# 8bitPig-BaconHomev2-frontPCB.net
KiCad netlist of a schematic drawn in EAGLE
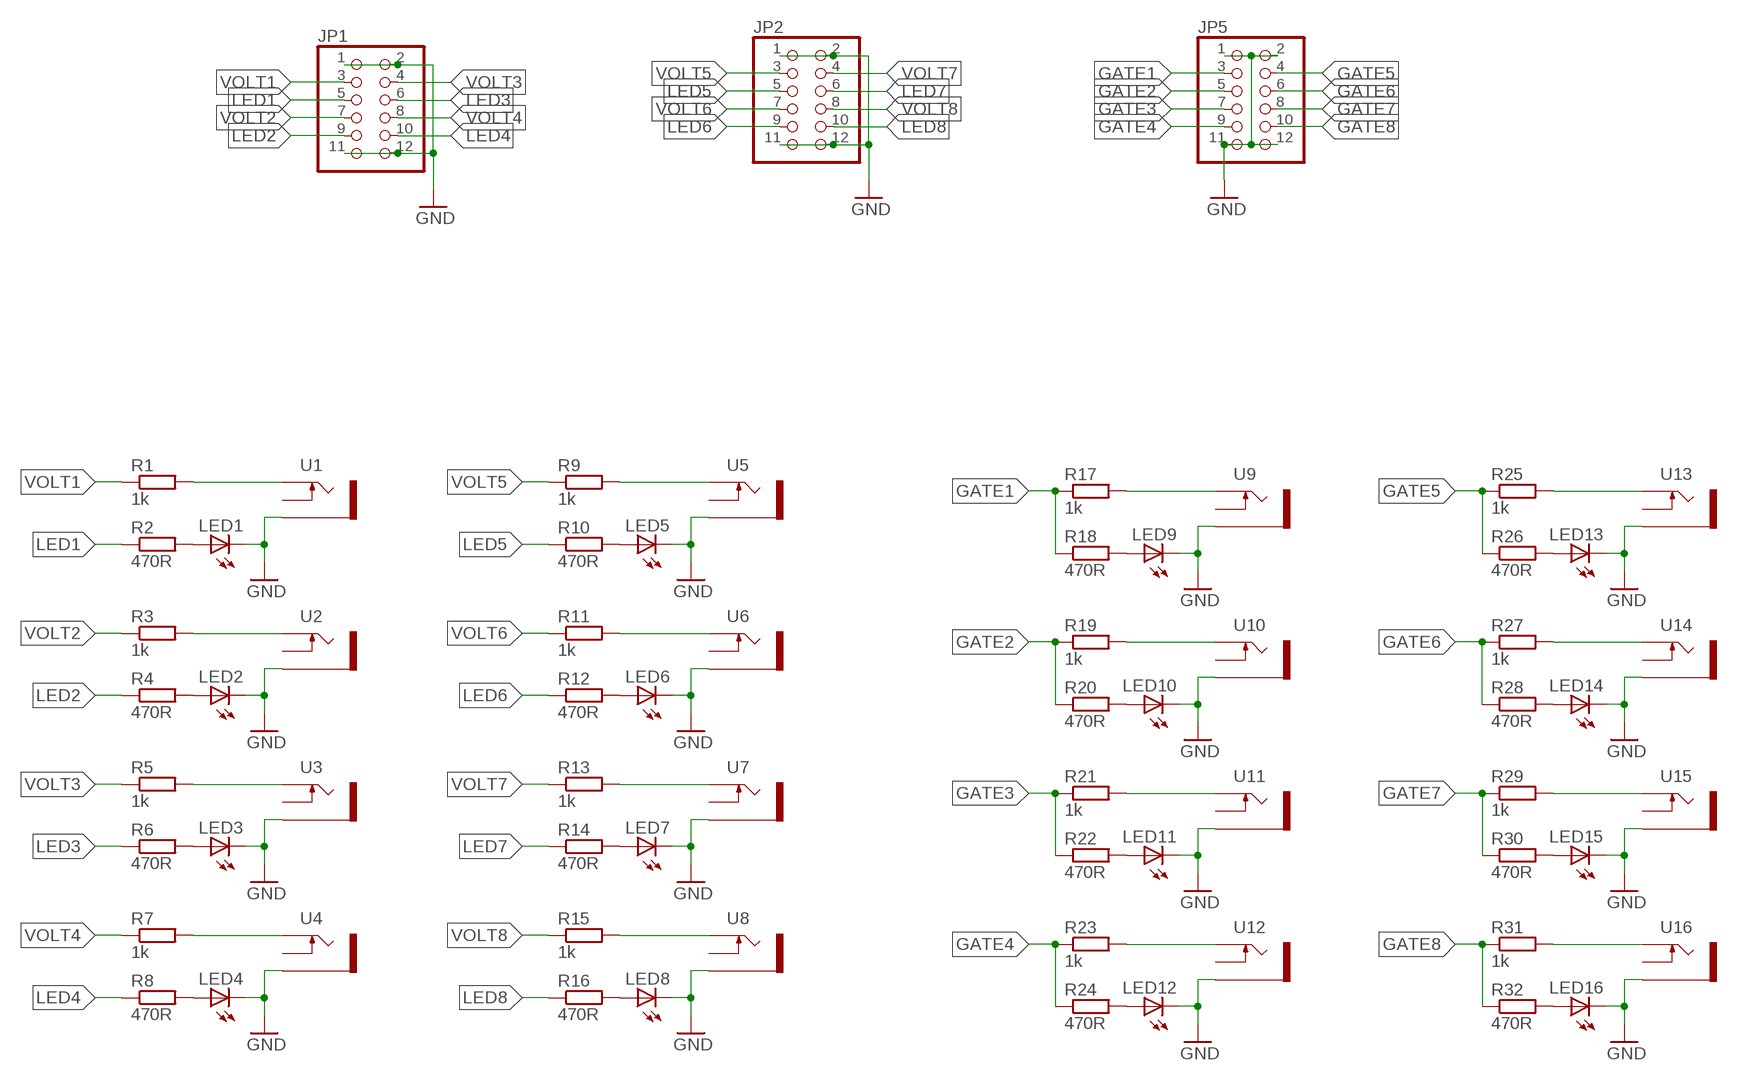
[diagram p0: schematic, sheet 1]

(export (version "E")
  (design (tool "Eeschema 10.0.6"))
  (components
    (comp (ref "JP1")
      (value "PINHD-2X6")
      (footprint "eagle-import:2X06")
      (libsource (lib "eagle-import") (part "PINHD-2X6"))
    )
    (comp (ref "JP2")
      (value "PINHD-2X6")
      (footprint "eagle-import:2X06")
      (libsource (lib "eagle-import") (part "PINHD-2X6"))
    )
    (comp (ref "JP5")
      (value "PINHD-2X6")
      (footprint "eagle-import:2X06")
      (libsource (lib "eagle-import") (part "PINHD-2X6"))
    )
    (comp (ref "LED1")
      (value "LED3MM")
      (footprint "eagle-import:LED3MM")
      (libsource (lib "eagle-import") (part "LED3MM"))
    )
    (comp (ref "LED2")
      (value "LED3MM")
      (footprint "eagle-import:LED3MM")
      (libsource (lib "eagle-import") (part "LED3MM"))
    )
    (comp (ref "LED3")
      (value "LED3MM")
      (footprint "eagle-import:LED3MM")
      (libsource (lib "eagle-import") (part "LED3MM"))
    )
    (comp (ref "LED4")
      (value "LED3MM")
      (footprint "eagle-import:LED3MM")
      (libsource (lib "eagle-import") (part "LED3MM"))
    )
    (comp (ref "LED5")
      (value "LED3MM")
      (footprint "eagle-import:LED3MM")
      (libsource (lib "eagle-import") (part "LED3MM"))
    )
    (comp (ref "LED6")
      (value "LED3MM")
      (footprint "eagle-import:LED3MM")
      (libsource (lib "eagle-import") (part "LED3MM"))
    )
    (comp (ref "LED7")
      (value "LED3MM")
      (footprint "eagle-import:LED3MM")
      (libsource (lib "eagle-import") (part "LED3MM"))
    )
    (comp (ref "LED8")
      (value "LED3MM")
      (footprint "eagle-import:LED3MM")
      (libsource (lib "eagle-import") (part "LED3MM"))
    )
    (comp (ref "LED9")
      (value "LED3MM")
      (footprint "eagle-import:LED3MM")
      (libsource (lib "eagle-import") (part "LED3MM"))
    )
    (comp (ref "LED10")
      (value "LED3MM")
      (footprint "eagle-import:LED3MM")
      (libsource (lib "eagle-import") (part "LED3MM"))
    )
    (comp (ref "LED11")
      (value "LED3MM")
      (footprint "eagle-import:LED3MM")
      (libsource (lib "eagle-import") (part "LED3MM"))
    )
    (comp (ref "LED12")
      (value "LED3MM")
      (footprint "eagle-import:LED3MM")
      (libsource (lib "eagle-import") (part "LED3MM"))
    )
    (comp (ref "LED13")
      (value "LED3MM")
      (footprint "eagle-import:LED3MM")
      (libsource (lib "eagle-import") (part "LED3MM"))
    )
    (comp (ref "LED14")
      (value "LED3MM")
      (footprint "eagle-import:LED3MM")
      (libsource (lib "eagle-import") (part "LED3MM"))
    )
    (comp (ref "LED15")
      (value "LED3MM")
      (footprint "eagle-import:LED3MM")
      (libsource (lib "eagle-import") (part "LED3MM"))
    )
    (comp (ref "LED16")
      (value "LED3MM")
      (footprint "eagle-import:LED3MM")
      (libsource (lib "eagle-import") (part "LED3MM"))
    )
    (comp (ref "R1")
      (value "1k")
      (footprint "eagle-import:R0603")
      (libsource (lib "eagle-import") (part "R-EU_R0603"))
    )
    (comp (ref "R2")
      (value "470R")
      (footprint "eagle-import:R0603")
      (libsource (lib "eagle-import") (part "R-EU_R0603"))
    )
    (comp (ref "R3")
      (value "1k")
      (footprint "eagle-import:R0603")
      (libsource (lib "eagle-import") (part "R-EU_R0603"))
    )
    (comp (ref "R4")
      (value "470R")
      (footprint "eagle-import:R0603")
      (libsource (lib "eagle-import") (part "R-EU_R0603"))
    )
    (comp (ref "R5")
      (value "1k")
      (footprint "eagle-import:R0603")
      (libsource (lib "eagle-import") (part "R-EU_R0603"))
    )
    (comp (ref "R6")
      (value "470R")
      (footprint "eagle-import:R0603")
      (libsource (lib "eagle-import") (part "R-EU_R0603"))
    )
    (comp (ref "R7")
      (value "1k")
      (footprint "eagle-import:R0603")
      (libsource (lib "eagle-import") (part "R-EU_R0603"))
    )
    (comp (ref "R8")
      (value "470R")
      (footprint "eagle-import:R0603")
      (libsource (lib "eagle-import") (part "R-EU_R0603"))
    )
    (comp (ref "R9")
      (value "1k")
      (footprint "eagle-import:R0603")
      (libsource (lib "eagle-import") (part "R-EU_R0603"))
    )
    (comp (ref "R10")
      (value "470R")
      (footprint "eagle-import:R0603")
      (libsource (lib "eagle-import") (part "R-EU_R0603"))
    )
    (comp (ref "R11")
      (value "1k")
      (footprint "eagle-import:R0603")
      (libsource (lib "eagle-import") (part "R-EU_R0603"))
    )
    (comp (ref "R12")
      (value "470R")
      (footprint "eagle-import:R0603")
      (libsource (lib "eagle-import") (part "R-EU_R0603"))
    )
    (comp (ref "R13")
      (value "1k")
      (footprint "eagle-import:R0603")
      (libsource (lib "eagle-import") (part "R-EU_R0603"))
    )
    (comp (ref "R14")
      (value "470R")
      (footprint "eagle-import:R0603")
      (libsource (lib "eagle-import") (part "R-EU_R0603"))
    )
    (comp (ref "R15")
      (value "1k")
      (footprint "eagle-import:R0603")
      (libsource (lib "eagle-import") (part "R-EU_R0603"))
    )
    (comp (ref "R16")
      (value "470R")
      (footprint "eagle-import:R0603")
      (libsource (lib "eagle-import") (part "R-EU_R0603"))
    )
    (comp (ref "R17")
      (value "1k")
      (footprint "eagle-import:R0603")
      (libsource (lib "eagle-import") (part "R-EU_R0603"))
    )
    (comp (ref "R18")
      (value "470R")
      (footprint "eagle-import:R0603")
      (libsource (lib "eagle-import") (part "R-EU_R0603"))
    )
    (comp (ref "R19")
      (value "1k")
      (footprint "eagle-import:R0603")
      (libsource (lib "eagle-import") (part "R-EU_R0603"))
    )
    (comp (ref "R20")
      (value "470R")
      (footprint "eagle-import:R0603")
      (libsource (lib "eagle-import") (part "R-EU_R0603"))
    )
    (comp (ref "R21")
      (value "1k")
      (footprint "eagle-import:R0603")
      (libsource (lib "eagle-import") (part "R-EU_R0603"))
    )
    (comp (ref "R22")
      (value "470R")
      (footprint "eagle-import:R0603")
      (libsource (lib "eagle-import") (part "R-EU_R0603"))
    )
    (comp (ref "R23")
      (value "1k")
      (footprint "eagle-import:R0603")
      (libsource (lib "eagle-import") (part "R-EU_R0603"))
    )
    (comp (ref "R24")
      (value "470R")
      (footprint "eagle-import:R0603")
      (libsource (lib "eagle-import") (part "R-EU_R0603"))
    )
    (comp (ref "R25")
      (value "1k")
      (footprint "eagle-import:R0603")
      (libsource (lib "eagle-import") (part "R-EU_R0603"))
    )
    (comp (ref "R26")
      (value "470R")
      (footprint "eagle-import:R0603")
      (libsource (lib "eagle-import") (part "R-EU_R0603"))
    )
    (comp (ref "R27")
      (value "1k")
      (footprint "eagle-import:R0603")
      (libsource (lib "eagle-import") (part "R-EU_R0603"))
    )
    (comp (ref "R28")
      (value "470R")
      (footprint "eagle-import:R0603")
      (libsource (lib "eagle-import") (part "R-EU_R0603"))
    )
    (comp (ref "R29")
      (value "1k")
      (footprint "eagle-import:R0603")
      (libsource (lib "eagle-import") (part "R-EU_R0603"))
    )
    (comp (ref "R30")
      (value "470R")
      (footprint "eagle-import:R0603")
      (libsource (lib "eagle-import") (part "R-EU_R0603"))
    )
    (comp (ref "R31")
      (value "1k")
      (footprint "eagle-import:R0603")
      (libsource (lib "eagle-import") (part "R-EU_R0603"))
    )
    (comp (ref "R32")
      (value "470R")
      (footprint "eagle-import:R0603")
      (libsource (lib "eagle-import") (part "R-EU_R0603"))
    )
    (comp (ref "U1")
      (value "THONKICONNNEW")
      (footprint "eagle-import:WQP-PJ301M-12_JACK")
      (libsource (lib "eagle-import") (part "THONKICONNNEW"))
    )
    (comp (ref "U2")
      (value "THONKICONNNEW")
      (footprint "eagle-import:WQP-PJ301M-12_JACK")
      (libsource (lib "eagle-import") (part "THONKICONNNEW"))
    )
    (comp (ref "U3")
      (value "THONKICONNNEW")
      (footprint "eagle-import:WQP-PJ301M-12_JACK")
      (libsource (lib "eagle-import") (part "THONKICONNNEW"))
    )
    (comp (ref "U4")
      (value "THONKICONNNEW")
      (footprint "eagle-import:WQP-PJ301M-12_JACK")
      (libsource (lib "eagle-import") (part "THONKICONNNEW"))
    )
    (comp (ref "U5")
      (value "THONKICONNNEW")
      (footprint "eagle-import:WQP-PJ301M-12_JACK")
      (libsource (lib "eagle-import") (part "THONKICONNNEW"))
    )
    (comp (ref "U6")
      (value "THONKICONNNEW")
      (footprint "eagle-import:WQP-PJ301M-12_JACK")
      (libsource (lib "eagle-import") (part "THONKICONNNEW"))
    )
    (comp (ref "U7")
      (value "THONKICONNNEW")
      (footprint "eagle-import:WQP-PJ301M-12_JACK")
      (libsource (lib "eagle-import") (part "THONKICONNNEW"))
    )
    (comp (ref "U8")
      (value "THONKICONNNEW")
      (footprint "eagle-import:WQP-PJ301M-12_JACK")
      (libsource (lib "eagle-import") (part "THONKICONNNEW"))
    )
    (comp (ref "U9")
      (value "THONKICONNNEW")
      (footprint "eagle-import:WQP-PJ301M-12_JACK")
      (libsource (lib "eagle-import") (part "THONKICONNNEW"))
    )
    (comp (ref "U10")
      (value "THONKICONNNEW")
      (footprint "eagle-import:WQP-PJ301M-12_JACK")
      (libsource (lib "eagle-import") (part "THONKICONNNEW"))
    )
    (comp (ref "U11")
      (value "THONKICONNNEW")
      (footprint "eagle-import:WQP-PJ301M-12_JACK")
      (libsource (lib "eagle-import") (part "THONKICONNNEW"))
    )
    (comp (ref "U12")
      (value "THONKICONNNEW")
      (footprint "eagle-import:WQP-PJ301M-12_JACK")
      (libsource (lib "eagle-import") (part "THONKICONNNEW"))
    )
    (comp (ref "U13")
      (value "THONKICONNNEW")
      (footprint "eagle-import:WQP-PJ301M-12_JACK")
      (libsource (lib "eagle-import") (part "THONKICONNNEW"))
    )
    (comp (ref "U14")
      (value "THONKICONNNEW")
      (footprint "eagle-import:WQP-PJ301M-12_JACK")
      (libsource (lib "eagle-import") (part "THONKICONNNEW"))
    )
    (comp (ref "U15")
      (value "THONKICONNNEW")
      (footprint "eagle-import:WQP-PJ301M-12_JACK")
      (libsource (lib "eagle-import") (part "THONKICONNNEW"))
    )
    (comp (ref "U16")
      (value "THONKICONNNEW")
      (footprint "eagle-import:WQP-PJ301M-12_JACK")
      (libsource (lib "eagle-import") (part "THONKICONNNEW"))
    )
  )
  (nets
    (net (code "1") (name "GATE1") (class "Default")
      (node (ref "JP5") (pin "3") (pinfunction "3_3") (pintype "passive"))
      (node (ref "R17") (pin "1") (pinfunction "1_1") (pintype "passive"))
      (node (ref "R18") (pin "1") (pinfunction "1_1") (pintype "passive"))
    )
    (net (code "2") (name "GATE2") (class "Default")
      (node (ref "JP5") (pin "5") (pinfunction "5_5") (pintype "passive"))
      (node (ref "R19") (pin "1") (pinfunction "1_1") (pintype "passive"))
      (node (ref "R20") (pin "1") (pinfunction "1_1") (pintype "passive"))
    )
    (net (code "3") (name "GATE3") (class "Default")
      (node (ref "JP5") (pin "7") (pinfunction "7_7") (pintype "passive"))
      (node (ref "R21") (pin "1") (pinfunction "1_1") (pintype "passive"))
      (node (ref "R22") (pin "1") (pinfunction "1_1") (pintype "passive"))
    )
    (net (code "4") (name "GATE4") (class "Default")
      (node (ref "JP5") (pin "9") (pinfunction "9_9") (pintype "passive"))
      (node (ref "R23") (pin "1") (pinfunction "1_1") (pintype "passive"))
      (node (ref "R24") (pin "1") (pinfunction "1_1") (pintype "passive"))
    )
    (net (code "5") (name "GATE5") (class "Default")
      (node (ref "JP5") (pin "4") (pinfunction "4_4") (pintype "passive"))
      (node (ref "R25") (pin "1") (pinfunction "1_1") (pintype "passive"))
      (node (ref "R26") (pin "1") (pinfunction "1_1") (pintype "passive"))
    )
    (net (code "6") (name "GATE6") (class "Default")
      (node (ref "JP5") (pin "6") (pinfunction "6_6") (pintype "passive"))
      (node (ref "R27") (pin "1") (pinfunction "1_1") (pintype "passive"))
      (node (ref "R28") (pin "1") (pinfunction "1_1") (pintype "passive"))
    )
    (net (code "7") (name "GATE7") (class "Default")
      (node (ref "JP5") (pin "8") (pinfunction "8_8") (pintype "passive"))
      (node (ref "R29") (pin "1") (pinfunction "1_1") (pintype "passive"))
      (node (ref "R30") (pin "1") (pinfunction "1_1") (pintype "passive"))
    )
    (net (code "8") (name "GATE8") (class "Default")
      (node (ref "JP5") (pin "10") (pinfunction "10_10") (pintype "passive"))
      (node (ref "R31") (pin "1") (pinfunction "1_1") (pintype "passive"))
      (node (ref "R32") (pin "1") (pinfunction "1_1") (pintype "passive"))
    )
    (net (code "9") (name "GND") (class "Default")
      (node (ref "JP1") (pin "1") (pinfunction "1_1") (pintype "passive"))
      (node (ref "JP1") (pin "11") (pinfunction "11_11") (pintype "passive"))
      (node (ref "JP1") (pin "12") (pinfunction "12_12") (pintype "passive"))
      (node (ref "JP1") (pin "2") (pinfunction "2_2") (pintype "passive"))
      (node (ref "JP2") (pin "1") (pinfunction "1_1") (pintype "passive"))
      (node (ref "JP2") (pin "11") (pinfunction "11_11") (pintype "passive"))
      (node (ref "JP2") (pin "12") (pinfunction "12_12") (pintype "passive"))
      (node (ref "JP2") (pin "2") (pinfunction "2_2") (pintype "passive"))
      (node (ref "JP5") (pin "1") (pinfunction "1_1") (pintype "passive"))
      (node (ref "JP5") (pin "11") (pinfunction "11_11") (pintype "passive"))
      (node (ref "JP5") (pin "12") (pinfunction "12_12") (pintype "passive"))
      (node (ref "JP5") (pin "2") (pinfunction "2_2") (pintype "passive"))
      (node (ref "LED1") (pin "K") (pinfunction "C_K") (pintype "passive"))
      (node (ref "LED10") (pin "K") (pinfunction "C_K") (pintype "passive"))
      (node (ref "LED11") (pin "K") (pinfunction "C_K") (pintype "passive"))
      (node (ref "LED12") (pin "K") (pinfunction "C_K") (pintype "passive"))
      (node (ref "LED13") (pin "K") (pinfunction "C_K") (pintype "passive"))
      (node (ref "LED14") (pin "K") (pinfunction "C_K") (pintype "passive"))
      (node (ref "LED15") (pin "K") (pinfunction "C_K") (pintype "passive"))
      (node (ref "LED16") (pin "K") (pinfunction "C_K") (pintype "passive"))
      (node (ref "LED2") (pin "K") (pinfunction "C_K") (pintype "passive"))
      (node (ref "LED3") (pin "K") (pinfunction "C_K") (pintype "passive"))
      (node (ref "LED4") (pin "K") (pinfunction "C_K") (pintype "passive"))
      (node (ref "LED5") (pin "K") (pinfunction "C_K") (pintype "passive"))
      (node (ref "LED6") (pin "K") (pinfunction "C_K") (pintype "passive"))
      (node (ref "LED7") (pin "K") (pinfunction "C_K") (pintype "passive"))
      (node (ref "LED8") (pin "K") (pinfunction "C_K") (pintype "passive"))
      (node (ref "LED9") (pin "K") (pinfunction "C_K") (pintype "passive"))
      (node (ref "U1") (pin "P$3_SLEEVE") (pinfunction "SLEEVE_P$3_SLEEVE") (pintype "passive"))
      (node (ref "U10") (pin "P$3_SLEEVE") (pinfunction "SLEEVE_P$3_SLEEVE") (pintype "passive"))
      (node (ref "U11") (pin "P$3_SLEEVE") (pinfunction "SLEEVE_P$3_SLEEVE") (pintype "passive"))
      (node (ref "U12") (pin "P$3_SLEEVE") (pinfunction "SLEEVE_P$3_SLEEVE") (pintype "passive"))
      (node (ref "U13") (pin "P$3_SLEEVE") (pinfunction "SLEEVE_P$3_SLEEVE") (pintype "passive"))
      (node (ref "U14") (pin "P$3_SLEEVE") (pinfunction "SLEEVE_P$3_SLEEVE") (pintype "passive"))
      (node (ref "U15") (pin "P$3_SLEEVE") (pinfunction "SLEEVE_P$3_SLEEVE") (pintype "passive"))
      (node (ref "U16") (pin "P$3_SLEEVE") (pinfunction "SLEEVE_P$3_SLEEVE") (pintype "passive"))
      (node (ref "U2") (pin "P$3_SLEEVE") (pinfunction "SLEEVE_P$3_SLEEVE") (pintype "passive"))
      (node (ref "U3") (pin "P$3_SLEEVE") (pinfunction "SLEEVE_P$3_SLEEVE") (pintype "passive"))
      (node (ref "U4") (pin "P$3_SLEEVE") (pinfunction "SLEEVE_P$3_SLEEVE") (pintype "passive"))
      (node (ref "U5") (pin "P$3_SLEEVE") (pinfunction "SLEEVE_P$3_SLEEVE") (pintype "passive"))
      (node (ref "U6") (pin "P$3_SLEEVE") (pinfunction "SLEEVE_P$3_SLEEVE") (pintype "passive"))
      (node (ref "U7") (pin "P$3_SLEEVE") (pinfunction "SLEEVE_P$3_SLEEVE") (pintype "passive"))
      (node (ref "U8") (pin "P$3_SLEEVE") (pinfunction "SLEEVE_P$3_SLEEVE") (pintype "passive"))
      (node (ref "U9") (pin "P$3_SLEEVE") (pinfunction "SLEEVE_P$3_SLEEVE") (pintype "passive"))
    )
    (net (code "10") (name "LED1") (class "Default")
      (node (ref "JP1") (pin "5") (pinfunction "5_5") (pintype "passive"))
      (node (ref "R2") (pin "1") (pinfunction "1_1") (pintype "passive"))
    )
    (net (code "11") (name "LED2") (class "Default")
      (node (ref "JP1") (pin "9") (pinfunction "9_9") (pintype "passive"))
      (node (ref "R4") (pin "1") (pinfunction "1_1") (pintype "passive"))
    )
    (net (code "12") (name "LED3") (class "Default")
      (node (ref "JP1") (pin "6") (pinfunction "6_6") (pintype "passive"))
      (node (ref "R6") (pin "1") (pinfunction "1_1") (pintype "passive"))
    )
    (net (code "13") (name "LED4") (class "Default")
      (node (ref "JP1") (pin "10") (pinfunction "10_10") (pintype "passive"))
      (node (ref "R8") (pin "1") (pinfunction "1_1") (pintype "passive"))
    )
    (net (code "14") (name "LED5") (class "Default")
      (node (ref "JP2") (pin "5") (pinfunction "5_5") (pintype "passive"))
      (node (ref "R10") (pin "1") (pinfunction "1_1") (pintype "passive"))
    )
    (net (code "15") (name "LED6") (class "Default")
      (node (ref "JP2") (pin "9") (pinfunction "9_9") (pintype "passive"))
      (node (ref "R12") (pin "1") (pinfunction "1_1") (pintype "passive"))
    )
    (net (code "16") (name "LED7") (class "Default")
      (node (ref "JP2") (pin "6") (pinfunction "6_6") (pintype "passive"))
      (node (ref "R14") (pin "1") (pinfunction "1_1") (pintype "passive"))
    )
    (net (code "17") (name "LED8") (class "Default")
      (node (ref "JP2") (pin "10") (pinfunction "10_10") (pintype "passive"))
      (node (ref "R16") (pin "1") (pinfunction "1_1") (pintype "passive"))
    )
    (net (code "18") (name "Net-(LED1-PadA)") (class "Default")
      (node (ref "LED1") (pin "A") (pinfunction "A_A") (pintype "passive"))
      (node (ref "R2") (pin "2") (pinfunction "2_2") (pintype "passive"))
    )
    (net (code "19") (name "Net-(LED2-PadA)") (class "Default")
      (node (ref "LED2") (pin "A") (pinfunction "A_A") (pintype "passive"))
      (node (ref "R4") (pin "2") (pinfunction "2_2") (pintype "passive"))
    )
    (net (code "20") (name "Net-(LED3-PadA)") (class "Default")
      (node (ref "LED3") (pin "A") (pinfunction "A_A") (pintype "passive"))
      (node (ref "R6") (pin "2") (pinfunction "2_2") (pintype "passive"))
    )
    (net (code "21") (name "Net-(LED4-PadA)") (class "Default")
      (node (ref "LED4") (pin "A") (pinfunction "A_A") (pintype "passive"))
      (node (ref "R8") (pin "2") (pinfunction "2_2") (pintype "passive"))
    )
    (net (code "22") (name "Net-(LED5-PadA)") (class "Default")
      (node (ref "LED5") (pin "A") (pinfunction "A_A") (pintype "passive"))
      (node (ref "R10") (pin "2") (pinfunction "2_2") (pintype "passive"))
    )
    (net (code "23") (name "Net-(LED6-PadA)") (class "Default")
      (node (ref "LED6") (pin "A") (pinfunction "A_A") (pintype "passive"))
      (node (ref "R12") (pin "2") (pinfunction "2_2") (pintype "passive"))
    )
    (net (code "24") (name "Net-(LED7-PadA)") (class "Default")
      (node (ref "LED7") (pin "A") (pinfunction "A_A") (pintype "passive"))
      (node (ref "R14") (pin "2") (pinfunction "2_2") (pintype "passive"))
    )
    (net (code "25") (name "Net-(LED8-PadA)") (class "Default")
      (node (ref "LED8") (pin "A") (pinfunction "A_A") (pintype "passive"))
      (node (ref "R16") (pin "2") (pinfunction "2_2") (pintype "passive"))
    )
    (net (code "26") (name "Net-(LED9-PadA)") (class "Default")
      (node (ref "LED9") (pin "A") (pinfunction "A_A") (pintype "passive"))
      (node (ref "R18") (pin "2") (pinfunction "2_2") (pintype "passive"))
    )
    (net (code "27") (name "Net-(LED10-PadA)") (class "Default")
      (node (ref "LED10") (pin "A") (pinfunction "A_A") (pintype "passive"))
      (node (ref "R20") (pin "2") (pinfunction "2_2") (pintype "passive"))
    )
    (net (code "28") (name "Net-(LED11-PadA)") (class "Default")
      (node (ref "LED11") (pin "A") (pinfunction "A_A") (pintype "passive"))
      (node (ref "R22") (pin "2") (pinfunction "2_2") (pintype "passive"))
    )
    (net (code "29") (name "Net-(LED12-PadA)") (class "Default")
      (node (ref "LED12") (pin "A") (pinfunction "A_A") (pintype "passive"))
      (node (ref "R24") (pin "2") (pinfunction "2_2") (pintype "passive"))
    )
    (net (code "30") (name "Net-(LED13-PadA)") (class "Default")
      (node (ref "LED13") (pin "A") (pinfunction "A_A") (pintype "passive"))
      (node (ref "R26") (pin "2") (pinfunction "2_2") (pintype "passive"))
    )
    (net (code "31") (name "Net-(LED14-PadA)") (class "Default")
      (node (ref "LED14") (pin "A") (pinfunction "A_A") (pintype "passive"))
      (node (ref "R28") (pin "2") (pinfunction "2_2") (pintype "passive"))
    )
    (net (code "32") (name "Net-(LED15-PadA)") (class "Default")
      (node (ref "LED15") (pin "A") (pinfunction "A_A") (pintype "passive"))
      (node (ref "R30") (pin "2") (pinfunction "2_2") (pintype "passive"))
    )
    (net (code "33") (name "Net-(LED16-PadA)") (class "Default")
      (node (ref "LED16") (pin "A") (pinfunction "A_A") (pintype "passive"))
      (node (ref "R32") (pin "2") (pinfunction "2_2") (pintype "passive"))
    )
    (net (code "34") (name "Net-(U1-TIP)") (class "Default")
      (node (ref "R1") (pin "2") (pinfunction "2_2") (pintype "passive"))
      (node (ref "U1") (pin "P$1_TIP") (pinfunction "TIP_P$1_TIP") (pintype "passive"))
    )
    (net (code "35") (name "Net-(U2-TIP)") (class "Default")
      (node (ref "R3") (pin "2") (pinfunction "2_2") (pintype "passive"))
      (node (ref "U2") (pin "P$1_TIP") (pinfunction "TIP_P$1_TIP") (pintype "passive"))
    )
    (net (code "36") (name "Net-(U3-TIP)") (class "Default")
      (node (ref "R5") (pin "2") (pinfunction "2_2") (pintype "passive"))
      (node (ref "U3") (pin "P$1_TIP") (pinfunction "TIP_P$1_TIP") (pintype "passive"))
    )
    (net (code "37") (name "Net-(U4-TIP)") (class "Default")
      (node (ref "R7") (pin "2") (pinfunction "2_2") (pintype "passive"))
      (node (ref "U4") (pin "P$1_TIP") (pinfunction "TIP_P$1_TIP") (pintype "passive"))
    )
    (net (code "38") (name "Net-(U5-TIP)") (class "Default")
      (node (ref "R9") (pin "2") (pinfunction "2_2") (pintype "passive"))
      (node (ref "U5") (pin "P$1_TIP") (pinfunction "TIP_P$1_TIP") (pintype "passive"))
    )
    (net (code "39") (name "Net-(U6-TIP)") (class "Default")
      (node (ref "R11") (pin "2") (pinfunction "2_2") (pintype "passive"))
      (node (ref "U6") (pin "P$1_TIP") (pinfunction "TIP_P$1_TIP") (pintype "passive"))
    )
    (net (code "40") (name "Net-(U7-TIP)") (class "Default")
      (node (ref "R13") (pin "2") (pinfunction "2_2") (pintype "passive"))
      (node (ref "U7") (pin "P$1_TIP") (pinfunction "TIP_P$1_TIP") (pintype "passive"))
    )
    (net (code "41") (name "Net-(U8-TIP)") (class "Default")
      (node (ref "R15") (pin "2") (pinfunction "2_2") (pintype "passive"))
      (node (ref "U8") (pin "P$1_TIP") (pinfunction "TIP_P$1_TIP") (pintype "passive"))
    )
    (net (code "42") (name "Net-(U9-TIP)") (class "Default")
      (node (ref "R17") (pin "2") (pinfunction "2_2") (pintype "passive"))
      (node (ref "U9") (pin "P$1_TIP") (pinfunction "TIP_P$1_TIP") (pintype "passive"))
    )
    (net (code "43") (name "Net-(U10-TIP)") (class "Default")
      (node (ref "R19") (pin "2") (pinfunction "2_2") (pintype "passive"))
      (node (ref "U10") (pin "P$1_TIP") (pinfunction "TIP_P$1_TIP") (pintype "passive"))
    )
    (net (code "44") (name "Net-(U11-TIP)") (class "Default")
      (node (ref "R21") (pin "2") (pinfunction "2_2") (pintype "passive"))
      (node (ref "U11") (pin "P$1_TIP") (pinfunction "TIP_P$1_TIP") (pintype "passive"))
    )
    (net (code "45") (name "Net-(U12-TIP)") (class "Default")
      (node (ref "R23") (pin "2") (pinfunction "2_2") (pintype "passive"))
      (node (ref "U12") (pin "P$1_TIP") (pinfunction "TIP_P$1_TIP") (pintype "passive"))
    )
    (net (code "46") (name "Net-(U13-TIP)") (class "Default")
      (node (ref "R25") (pin "2") (pinfunction "2_2") (pintype "passive"))
      (node (ref "U13") (pin "P$1_TIP") (pinfunction "TIP_P$1_TIP") (pintype "passive"))
    )
    (net (code "47") (name "Net-(U14-TIP)") (class "Default")
      (node (ref "R27") (pin "2") (pinfunction "2_2") (pintype "passive"))
      (node (ref "U14") (pin "P$1_TIP") (pinfunction "TIP_P$1_TIP") (pintype "passive"))
    )
    (net (code "48") (name "Net-(U15-TIP)") (class "Default")
      (node (ref "R29") (pin "2") (pinfunction "2_2") (pintype "passive"))
      (node (ref "U15") (pin "P$1_TIP") (pinfunction "TIP_P$1_TIP") (pintype "passive"))
    )
    (net (code "49") (name "Net-(U16-TIP)") (class "Default")
      (node (ref "R31") (pin "2") (pinfunction "2_2") (pintype "passive"))
      (node (ref "U16") (pin "P$1_TIP") (pinfunction "TIP_P$1_TIP") (pintype "passive"))
    )
    (net (code "50") (name "VOLT1") (class "Default")
      (node (ref "JP1") (pin "3") (pinfunction "3_3") (pintype "passive"))
      (node (ref "R1") (pin "1") (pinfunction "1_1") (pintype "passive"))
    )
    (net (code "51") (name "VOLT2") (class "Default")
      (node (ref "JP1") (pin "7") (pinfunction "7_7") (pintype "passive"))
      (node (ref "R3") (pin "1") (pinfunction "1_1") (pintype "passive"))
    )
    (net (code "52") (name "VOLT3") (class "Default")
      (node (ref "JP1") (pin "4") (pinfunction "4_4") (pintype "passive"))
      (node (ref "R5") (pin "1") (pinfunction "1_1") (pintype "passive"))
    )
    (net (code "53") (name "VOLT4") (class "Default")
      (node (ref "JP1") (pin "8") (pinfunction "8_8") (pintype "passive"))
      (node (ref "R7") (pin "1") (pinfunction "1_1") (pintype "passive"))
    )
    (net (code "54") (name "VOLT5") (class "Default")
      (node (ref "JP2") (pin "3") (pinfunction "3_3") (pintype "passive"))
      (node (ref "R9") (pin "1") (pinfunction "1_1") (pintype "passive"))
    )
    (net (code "55") (name "VOLT6") (class "Default")
      (node (ref "JP2") (pin "7") (pinfunction "7_7") (pintype "passive"))
      (node (ref "R11") (pin "1") (pinfunction "1_1") (pintype "passive"))
    )
    (net (code "56") (name "VOLT7") (class "Default")
      (node (ref "JP2") (pin "4") (pinfunction "4_4") (pintype "passive"))
      (node (ref "R13") (pin "1") (pinfunction "1_1") (pintype "passive"))
    )
    (net (code "57") (name "VOLT8") (class "Default")
      (node (ref "JP2") (pin "8") (pinfunction "8_8") (pintype "passive"))
      (node (ref "R15") (pin "1") (pinfunction "1_1") (pintype "passive"))
    )
    (net (code "58") (name "unconnected-(U1-SWITCH-PadP$2_SWITCH)") (class "Default")
      (node (ref "U1") (pin "P$2_SWITCH") (pinfunction "SWITCH_P$2_SWITCH") (pintype "passive"))
    )
    (net (code "59") (name "unconnected-(U2-SWITCH-PadP$2_SWITCH)") (class "Default")
      (node (ref "U2") (pin "P$2_SWITCH") (pinfunction "SWITCH_P$2_SWITCH") (pintype "passive"))
    )
    (net (code "60") (name "unconnected-(U3-SWITCH-PadP$2_SWITCH)") (class "Default")
      (node (ref "U3") (pin "P$2_SWITCH") (pinfunction "SWITCH_P$2_SWITCH") (pintype "passive"))
    )
    (net (code "61") (name "unconnected-(U4-SWITCH-PadP$2_SWITCH)") (class "Default")
      (node (ref "U4") (pin "P$2_SWITCH") (pinfunction "SWITCH_P$2_SWITCH") (pintype "passive"))
    )
    (net (code "62") (name "unconnected-(U5-SWITCH-PadP$2_SWITCH)") (class "Default")
      (node (ref "U5") (pin "P$2_SWITCH") (pinfunction "SWITCH_P$2_SWITCH") (pintype "passive"))
    )
    (net (code "63") (name "unconnected-(U6-SWITCH-PadP$2_SWITCH)") (class "Default")
      (node (ref "U6") (pin "P$2_SWITCH") (pinfunction "SWITCH_P$2_SWITCH") (pintype "passive"))
    )
    (net (code "64") (name "unconnected-(U7-SWITCH-PadP$2_SWITCH)") (class "Default")
      (node (ref "U7") (pin "P$2_SWITCH") (pinfunction "SWITCH_P$2_SWITCH") (pintype "passive"))
    )
    (net (code "65") (name "unconnected-(U8-SWITCH-PadP$2_SWITCH)") (class "Default")
      (node (ref "U8") (pin "P$2_SWITCH") (pinfunction "SWITCH_P$2_SWITCH") (pintype "passive"))
    )
    (net (code "66") (name "unconnected-(U9-SWITCH-PadP$2_SWITCH)") (class "Default")
      (node (ref "U9") (pin "P$2_SWITCH") (pinfunction "SWITCH_P$2_SWITCH") (pintype "passive"))
    )
    (net (code "67") (name "unconnected-(U10-SWITCH-PadP$2_SWITCH)") (class "Default")
      (node (ref "U10") (pin "P$2_SWITCH") (pinfunction "SWITCH_P$2_SWITCH") (pintype "passive"))
    )
    (net (code "68") (name "unconnected-(U11-SWITCH-PadP$2_SWITCH)") (class "Default")
      (node (ref "U11") (pin "P$2_SWITCH") (pinfunction "SWITCH_P$2_SWITCH") (pintype "passive"))
    )
    (net (code "69") (name "unconnected-(U12-SWITCH-PadP$2_SWITCH)") (class "Default")
      (node (ref "U12") (pin "P$2_SWITCH") (pinfunction "SWITCH_P$2_SWITCH") (pintype "passive"))
    )
    (net (code "70") (name "unconnected-(U13-SWITCH-PadP$2_SWITCH)") (class "Default")
      (node (ref "U13") (pin "P$2_SWITCH") (pinfunction "SWITCH_P$2_SWITCH") (pintype "passive"))
    )
    (net (code "71") (name "unconnected-(U14-SWITCH-PadP$2_SWITCH)") (class "Default")
      (node (ref "U14") (pin "P$2_SWITCH") (pinfunction "SWITCH_P$2_SWITCH") (pintype "passive"))
    )
    (net (code "72") (name "unconnected-(U15-SWITCH-PadP$2_SWITCH)") (class "Default")
      (node (ref "U15") (pin "P$2_SWITCH") (pinfunction "SWITCH_P$2_SWITCH") (pintype "passive"))
    )
    (net (code "73") (name "unconnected-(U16-SWITCH-PadP$2_SWITCH)") (class "Default")
      (node (ref "U16") (pin "P$2_SWITCH") (pinfunction "SWITCH_P$2_SWITCH") (pintype "passive"))
    )
  )
)
